# Emech.net
KiCad netlist of a schematic drawn in Altium Designer
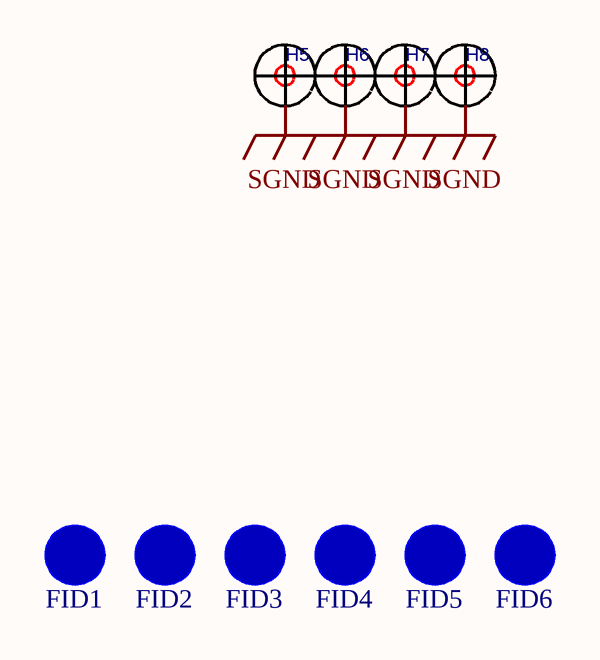
[diagram p0: Emech.SchDoc]

(export (version "E")
  (design (tool "Eeschema 10.0.6"))
  (components
    (comp (ref "FID1")
      (value "FID_1MM_SMALL")
      (footprint "FID_40X52D")
      (description "Fiducial 40mil Diameter, 52mil Mask")
      (libsource (lib "DrvBoard") (part "FID_1MM_SMALL"))
    )
    (comp (ref "FID2")
      (value "FID_1MM_SMALL")
      (footprint "FID_40X52D")
      (description "Fiducial 40mil Diameter, 52mil Mask")
      (libsource (lib "DrvBoard") (part "FID_1MM_SMALL"))
    )
    (comp (ref "FID3")
      (value "FID_1MM_SMALL")
      (footprint "FID_40X52D")
      (description "Fiducial 40mil Diameter, 52mil Mask")
      (libsource (lib "DrvBoard") (part "FID_1MM_SMALL"))
    )
    (comp (ref "FID4")
      (value "FID_1MM_SMALL")
      (footprint "FID_40X52D")
      (description "Fiducial 40mil Diameter, 52mil Mask")
      (libsource (lib "DrvBoard") (part "FID_1MM_SMALL"))
    )
    (comp (ref "FID5")
      (value "FID_1MM_SMALL")
      (footprint "FID_40X52D")
      (description "Fiducial 40mil Diameter, 52mil Mask")
      (libsource (lib "DrvBoard") (part "FID_1MM_SMALL"))
    )
    (comp (ref "FID6")
      (value "FID_1MM_SMALL")
      (footprint "FID_40X52D")
      (description "Fiducial 40mil Diameter, 52mil Mask")
      (libsource (lib "DrvBoard") (part "FID_1MM_SMALL"))
    )
    (comp (ref "H5") (value "HOLE") (footprint "HOLE_Φ3_3") (libsource (lib "小车") (part "HOLE")))
    (comp (ref "H6") (value "HOLE") (footprint "HOLE_Φ3_3") (libsource (lib "小车") (part "HOLE")))
    (comp (ref "H7") (value "HOLE") (footprint "HOLE_Φ3_3") (libsource (lib "小车") (part "HOLE")))
    (comp (ref "H8") (value "HOLE") (footprint "HOLE_Φ3_3") (libsource (lib "小车") (part "HOLE")))
  )
  (nets
    (net (code "1") (name "SGND") (class "Default")
      (node (ref "H5") (pin "1") (pintype "passive"))
      (node (ref "H6") (pin "1") (pintype "passive"))
      (node (ref "H7") (pin "1") (pintype "passive"))
      (node (ref "H8") (pin "1") (pintype "passive"))
    )
  )
)
